# LED.net
KiCad netlist of a schematic drawn in Altium Designer
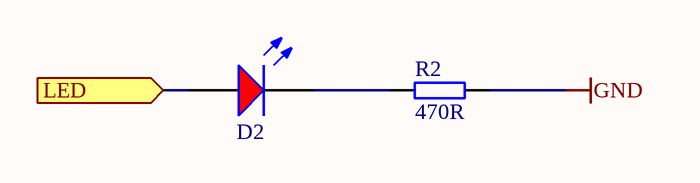
[diagram p0: LED.SchDoc]

(export (version "E")
  (design (tool "Eeschema 10.0.6"))
  (components
    (comp (ref "D2")
      (value "LED Red")
      (footprint "WL-SMCW_0603")
      (description "Standard LEDs - SMD 0603 red")
      (fields
        (field (name "MANUFACTURER PART NUMBER") "UZgen_LED_0603_Red")
        (field (name "MANUFACTURER") "UZgen")
        (field (name "CREATED FROM") "UZgenTool")
      )
      (libsource (lib "user") (part "LED_Red"))
    )
    (comp (ref "R2")
      (value "470R")
      (footprint "R_0603_TE")
      (description "Generic resistor")
      (fields
        (field (name "MANUFACTURER PART NUMBER") "UZgen_R_0603_470R")
        (field (name "MANUFACTURER") "UZgen")
        (field (name "CREATED FROM") "UZgenTool")
      )
      (libsource (lib "user") (part "RES"))
    )
  )
  (nets
    (net (code "1") (name "/LED") (class "Default")
      (node (ref "D2") (pin "2") (pinfunction "A_2") (pintype "passive"))
    )
    (net (code "2") (name "GND") (class "Default")
      (node (ref "R2") (pin "2") (pinfunction "2_2") (pintype "passive"))
    )
    (net (code "3") (name "Net-(D2-K)") (class "Default")
      (node (ref "D2") (pin "1") (pinfunction "K_1") (pintype "passive"))
      (node (ref "R2") (pin "1") (pinfunction "1_1") (pintype "passive"))
    )
  )
)
